# pidshield-mk-3_0.net
KiCad netlist of a schematic drawn in EAGLE
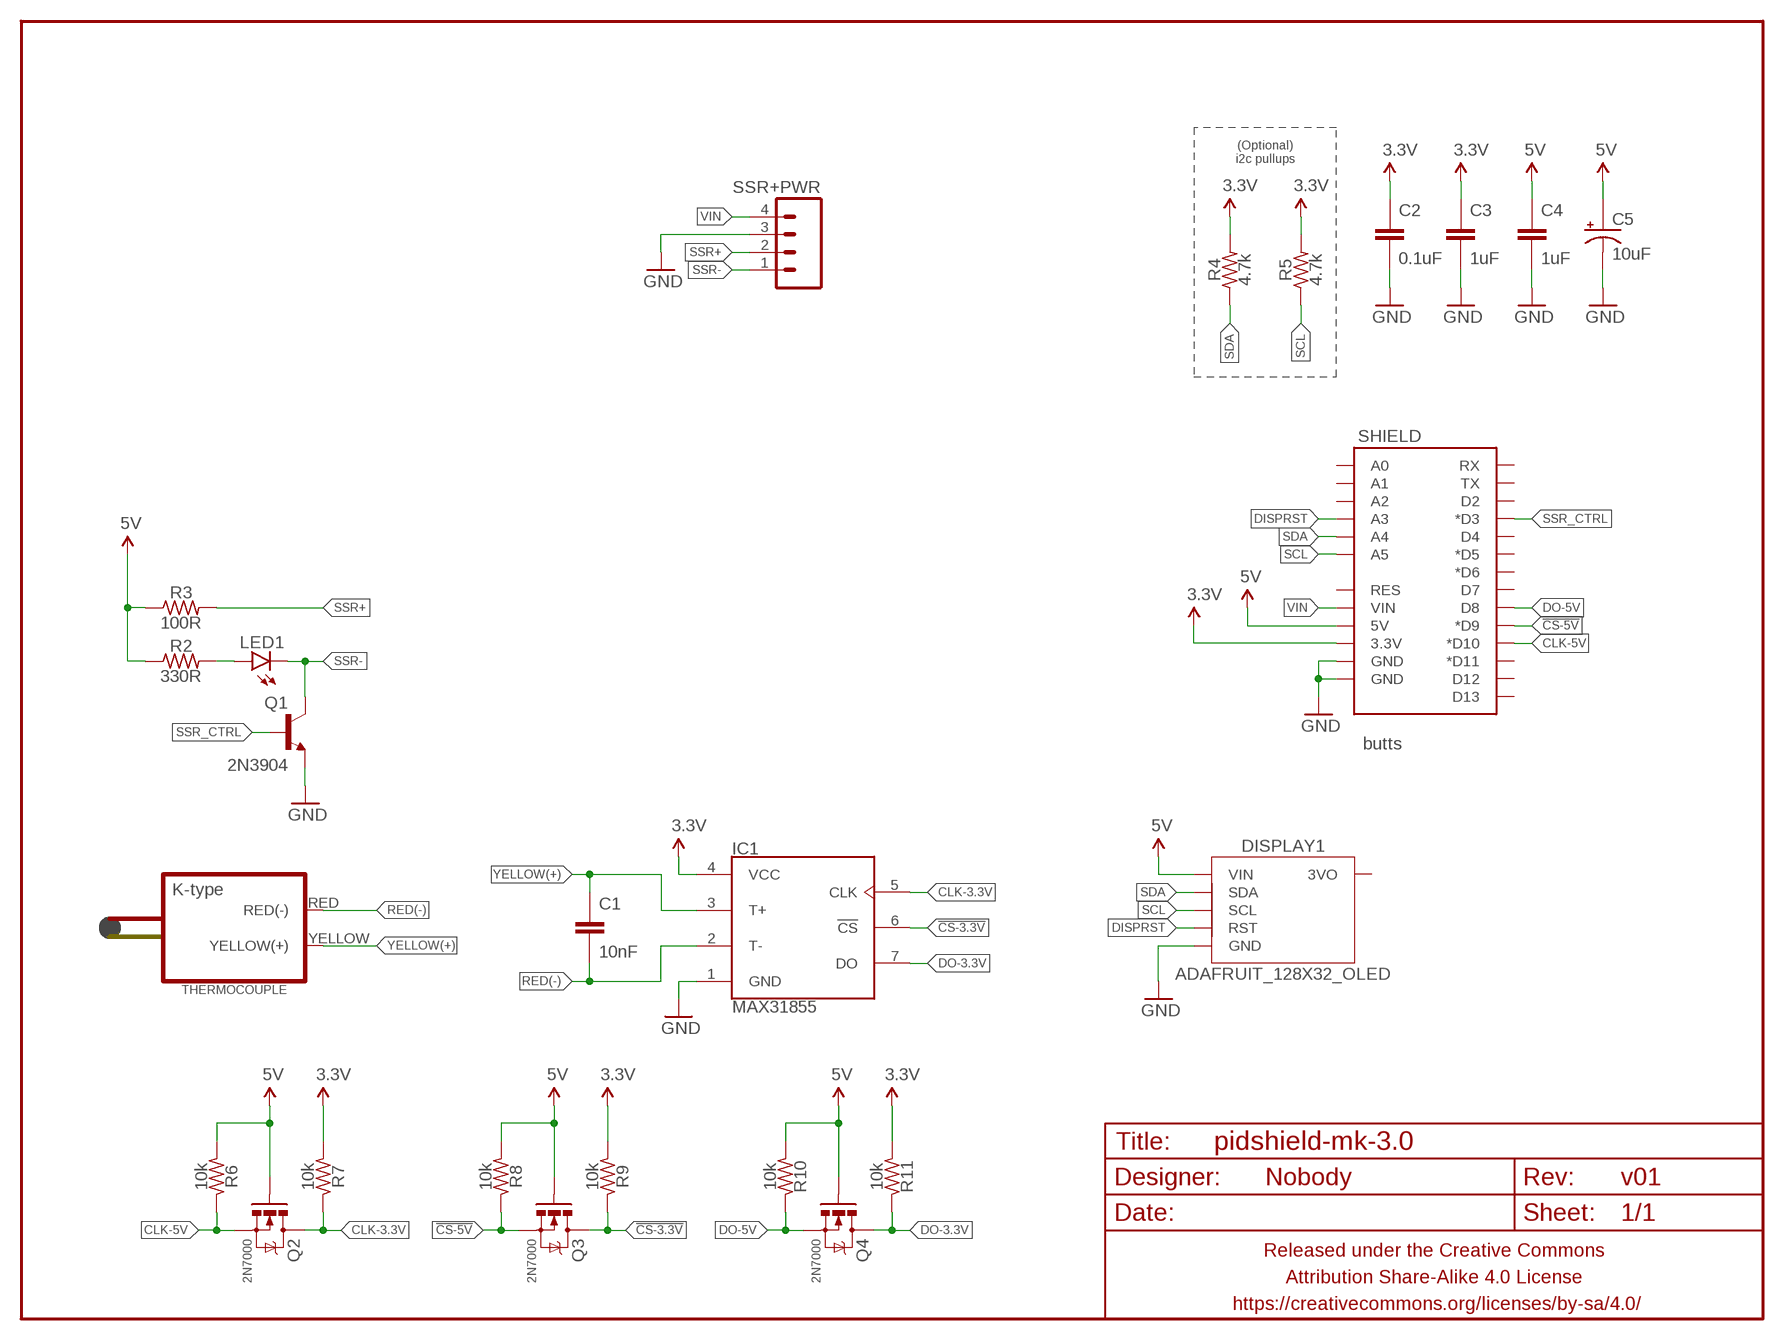
[diagram p0: schematic, sheet 1]

(export (version "E")
  (design (tool "Eeschema 10.0.6"))
  (components
    (comp (ref "C1")
      (value "10nF")
      (footprint "eagle-import:C0805")
      (libsource (lib "eagle-import") (part "CAPACITOR-CERAMICC0805"))
    )
    (comp (ref "C2")
      (value "0.1uF")
      (footprint "eagle-import:C025-024X044")
      (libsource (lib "eagle-import") (part "CAPACITOR-CERAMIC025-024X044"))
    )
    (comp (ref "C3")
      (value "1uF")
      (footprint "eagle-import:C025-024X044")
      (libsource (lib "eagle-import") (part "CAPACITOR-CERAMIC025-024X044"))
    )
    (comp (ref "C4")
      (value "1uF")
      (footprint "eagle-import:C025-024X044")
      (libsource (lib "eagle-import") (part "CAPACITOR-CERAMIC025-024X044"))
    )
    (comp (ref "C5")
      (value "10uF")
      (footprint "eagle-import:E2,5-6")
      (libsource (lib "eagle-import") (part "CAPACITOR-POLARIZEDE2.5-6"))
    )
    (comp (ref "DISPLAY1")
      (value "ADAFRUIT_128X32_OLED")
      (footprint "eagle-import:ADAFRUIT_128X32_OLED_I2C_CLOSER_NS")
      (libsource (lib "eagle-import") (part "ADAFRUIT_128X32_OLED_I2CNOSILK_NOHOLES_NOPROBLEM"))
    )
    (comp (ref "FRAME1")
      (value "FRAME-LETTERNO_PACKAGE")
      (footprint "eagle-import:DUMMY")
      (fields (field (name "DESIGNER") "Nobody"))
      (libsource (lib "eagle-import") (part "FRAME-LETTERNO_PACKAGE"))
    )
    (comp (ref "IC1")
      (value "MAX31855")
      (footprint "eagle-import:SOIC127P600X175-8N")
      (libsource (lib "eagle-import") (part "MAX31855SOIC"))
    )
    (comp (ref "LED1")
      (value "LED3MM-LESS")
      (footprint "eagle-import:LED3MM-LESSSILK")
      (libsource (lib "eagle-import") (part "LED3MM-LESS"))
    )
    (comp (ref "Q1")
      (value "2N3904")
      (footprint "eagle-import:TO-92-AMMO")
      (libsource (lib "eagle-import") (part "TRANSISTOR_NPNTO-92-AMMO-EBC"))
    )
    (comp (ref "Q2")
      (value "2N7000")
      (footprint "eagle-import:TO-92-AMMO")
      (libsource (lib "eagle-import") (part "MOSFET-NCHANNEL2N7000-AMMO"))
    )
    (comp (ref "Q3")
      (value "2N7000")
      (footprint "eagle-import:TO-92-AMMO")
      (libsource (lib "eagle-import") (part "MOSFET-NCHANNEL2N7000-AMMO"))
    )
    (comp (ref "Q4")
      (value "2N7000")
      (footprint "eagle-import:TO-92-AMMO")
      (libsource (lib "eagle-import") (part "MOSFET-NCHANNEL2N7000-AMMO"))
    )
    (comp (ref "R2")
      (value "330R")
      (footprint "eagle-import:RESISTOR-AXIAL-PTH-5.08MM")
      (libsource (lib "eagle-import") (part "RESISTORPTH-AXIAL-5.08MM"))
    )
    (comp (ref "R3")
      (value "100R")
      (footprint "eagle-import:RESISTOR-AXIAL-PTH-5.08MM")
      (libsource (lib "eagle-import") (part "RESISTORPTH-AXIAL-5.08MM"))
    )
    (comp (ref "R4")
      (value "4.7k")
      (footprint "eagle-import:RESISTOR-AXIAL-PTH-5.08MM")
      (libsource (lib "eagle-import") (part "RESISTORPTH-AXIAL-5.08MM"))
    )
    (comp (ref "R5")
      (value "4.7k")
      (footprint "eagle-import:RESISTOR-AXIAL-PTH-5.08MM")
      (libsource (lib "eagle-import") (part "RESISTORPTH-AXIAL-5.08MM"))
    )
    (comp (ref "R6")
      (value "10k")
      (footprint "eagle-import:RESISTOR-AXIAL-PTH-5.08MM")
      (libsource (lib "eagle-import") (part "RESISTORPTH-AXIAL-5.08MM"))
    )
    (comp (ref "R7")
      (value "10k")
      (footprint "eagle-import:RESISTOR-AXIAL-PTH-5.08MM")
      (libsource (lib "eagle-import") (part "RESISTORPTH-AXIAL-5.08MM"))
    )
    (comp (ref "R8")
      (value "10k")
      (footprint "eagle-import:RESISTOR-AXIAL-PTH-5.08MM")
      (libsource (lib "eagle-import") (part "RESISTORPTH-AXIAL-5.08MM"))
    )
    (comp (ref "R9")
      (value "10k")
      (footprint "eagle-import:RESISTOR-AXIAL-PTH-5.08MM")
      (libsource (lib "eagle-import") (part "RESISTORPTH-AXIAL-5.08MM"))
    )
    (comp (ref "R10")
      (value "10k")
      (footprint "eagle-import:RESISTOR-AXIAL-PTH-5.08MM")
      (libsource (lib "eagle-import") (part "RESISTORPTH-AXIAL-5.08MM"))
    )
    (comp (ref "R11")
      (value "10k")
      (footprint "eagle-import:RESISTOR-AXIAL-PTH-5.08MM")
      (libsource (lib "eagle-import") (part "RESISTORPTH-AXIAL-5.08MM"))
    )
    (comp (ref "SHIELD")
      (value "butts")
      (footprint "eagle-import:ARDUINO_SHIELD_SMALLER_NEKKID")
      (libsource (lib "eagle-import") (part "ARDUINO_SHIELD_SMALLERNEKKID"))
    )
    (comp (ref "SSR+PWR")
      (value "M04JST_XH_RA")
      (footprint "eagle-import:JST-4-XH-RA-PTH")
      (libsource (lib "eagle-import") (part "M04JST_XH_RA"))
    )
    (comp (ref "THERMOCOUPLE")
      (value "THERMOCOUPLE-CONNECTORMINI-PCB")
      (footprint "eagle-import:PCC-SMP")
      (libsource (lib "eagle-import") (part "THERMOCOUPLE-CONNECTORMINI-PCB"))
    )
  )
  (nets
    (net (code "1") (name "/~{CS-3.3V}") (class "Default")
      (node (ref "IC1") (pin "6") (pinfunction "~{CS}_6") (pintype "input"))
      (node (ref "Q3") (pin "3") (pinfunction "D_3") (pintype "passive"))
      (node (ref "R9") (pin "P$1") (pinfunction "1_P$1") (pintype "passive"))
    )
    (net (code "2") (name "/~{CS-5V}") (class "Default")
      (node (ref "Q3") (pin "1") (pinfunction "S_1") (pintype "passive"))
      (node (ref "R8") (pin "P$1") (pinfunction "1_P$1") (pintype "passive"))
      (node (ref "SHIELD") (pin "D9") (pinfunction "*D9_D9") (pintype "bidirectional"))
    )
    (net (code "3") (name "3.3V") (class "Default")
      (node (ref "C2") (pin "1") (pinfunction "1_1") (pintype "passive"))
      (node (ref "C3") (pin "1") (pinfunction "1_1") (pintype "passive"))
      (node (ref "IC1") (pin "4") (pinfunction "VCC_4") (pintype "power_in"))
      (node (ref "R11") (pin "P$2") (pinfunction "2_P$2") (pintype "passive"))
      (node (ref "R4") (pin "P$2") (pinfunction "2_P$2") (pintype "passive"))
      (node (ref "R5") (pin "P$2") (pinfunction "2_P$2") (pintype "passive"))
      (node (ref "R7") (pin "P$2") (pinfunction "2_P$2") (pintype "passive"))
      (node (ref "R9") (pin "P$2") (pinfunction "2_P$2") (pintype "passive"))
      (node (ref "SHIELD") (pin "3.3V") (pinfunction "3.3V_3.3V") (pintype "bidirectional"))
    )
    (net (code "4") (name "5V") (class "Default")
      (node (ref "C4") (pin "1") (pinfunction "1_1") (pintype "passive"))
      (node (ref "C5") (pin "+") (pinfunction "+_+") (pintype "passive"))
      (node (ref "DISPLAY1") (pin "VIN") (pinfunction "VIN_VIN") (pintype "bidirectional"))
      (node (ref "Q2") (pin "2") (pinfunction "G_2") (pintype "passive"))
      (node (ref "Q3") (pin "2") (pinfunction "G_2") (pintype "passive"))
      (node (ref "Q4") (pin "2") (pinfunction "G_2") (pintype "passive"))
      (node (ref "R10") (pin "P$2") (pinfunction "2_P$2") (pintype "passive"))
      (node (ref "R2") (pin "P$1") (pinfunction "1_P$1") (pintype "passive"))
      (node (ref "R3") (pin "P$1") (pinfunction "1_P$1") (pintype "passive"))
      (node (ref "R6") (pin "P$2") (pinfunction "2_P$2") (pintype "passive"))
      (node (ref "R8") (pin "P$2") (pinfunction "2_P$2") (pintype "passive"))
      (node (ref "SHIELD") (pin "5V") (pinfunction "5V_5V") (pintype "bidirectional"))
    )
    (net (code "5") (name "CLK-3.3V") (class "Default")
      (node (ref "IC1") (pin "5") (pinfunction "CLK_5") (pintype "input"))
      (node (ref "Q2") (pin "3") (pinfunction "D_3") (pintype "passive"))
      (node (ref "R7") (pin "P$1") (pinfunction "1_P$1") (pintype "passive"))
    )
    (net (code "6") (name "CLK-5V") (class "Default")
      (node (ref "Q2") (pin "1") (pinfunction "S_1") (pintype "passive"))
      (node (ref "R6") (pin "P$1") (pinfunction "1_P$1") (pintype "passive"))
      (node (ref "SHIELD") (pin "D10") (pinfunction "*D10_D10") (pintype "bidirectional"))
    )
    (net (code "7") (name "DISPRST") (class "Default")
      (node (ref "DISPLAY1") (pin "RST") (pinfunction "RST_RST") (pintype "bidirectional"))
      (node (ref "SHIELD") (pin "A3") (pinfunction "A3_A3") (pintype "bidirectional"))
    )
    (net (code "8") (name "DO-3.3V") (class "Default")
      (node (ref "IC1") (pin "7") (pinfunction "DO_7") (pintype "output"))
      (node (ref "Q4") (pin "3") (pinfunction "D_3") (pintype "passive"))
      (node (ref "R11") (pin "P$1") (pinfunction "1_P$1") (pintype "passive"))
    )
    (net (code "9") (name "DO-5V") (class "Default")
      (node (ref "Q4") (pin "1") (pinfunction "S_1") (pintype "passive"))
      (node (ref "R10") (pin "P$1") (pinfunction "1_P$1") (pintype "passive"))
      (node (ref "SHIELD") (pin "D8") (pinfunction "D8_D8") (pintype "bidirectional"))
    )
    (net (code "10") (name "GND") (class "Default")
      (node (ref "C2") (pin "2") (pinfunction "2_2") (pintype "passive"))
      (node (ref "C3") (pin "2") (pinfunction "2_2") (pintype "passive"))
      (node (ref "C4") (pin "2") (pinfunction "2_2") (pintype "passive"))
      (node (ref "C5") (pin "-") (pinfunction "-_-") (pintype "passive"))
      (node (ref "DISPLAY1") (pin "GND") (pinfunction "GND_GND") (pintype "bidirectional"))
      (node (ref "IC1") (pin "1") (pinfunction "GND_1") (pintype "power_in"))
      (node (ref "Q1") (pin "1") (pinfunction "E_1") (pintype "passive"))
      (node (ref "SHIELD") (pin "GND@0") (pinfunction "GND_GND@0") (pintype "bidirectional"))
      (node (ref "SHIELD") (pin "GND@1") (pinfunction "GND_GND@1") (pintype "bidirectional"))
      (node (ref "SSR+PWR") (pin "3") (pinfunction "3_3") (pintype "passive"))
    )
    (net (code "11") (name "Net-(R2-2)") (class "Default")
      (node (ref "LED1") (pin "A") (pinfunction "A_A") (pintype "passive"))
      (node (ref "R2") (pin "P$2") (pinfunction "2_P$2") (pintype "passive"))
    )
    (net (code "12") (name "RED(-)") (class "Default")
      (node (ref "C1") (pin "2") (pinfunction "2_2") (pintype "passive"))
      (node (ref "IC1") (pin "2") (pinfunction "T-_2") (pintype "input"))
      (node (ref "THERMOCOUPLE") (pin "RED") (pinfunction "RED(-)_RED") (pintype "bidirectional"))
    )
    (net (code "13") (name "SCL") (class "Default")
      (node (ref "DISPLAY1") (pin "SCL") (pinfunction "SCL_SCL") (pintype "bidirectional"))
      (node (ref "R5") (pin "P$1") (pinfunction "1_P$1") (pintype "passive"))
      (node (ref "SHIELD") (pin "A5") (pinfunction "A5_A5") (pintype "bidirectional"))
    )
    (net (code "14") (name "SDA") (class "Default")
      (node (ref "DISPLAY1") (pin "SDA") (pinfunction "SDA_SDA") (pintype "bidirectional"))
      (node (ref "R4") (pin "P$1") (pinfunction "1_P$1") (pintype "passive"))
      (node (ref "SHIELD") (pin "A4") (pinfunction "A4_A4") (pintype "bidirectional"))
    )
    (net (code "15") (name "SSR+") (class "Default")
      (node (ref "R3") (pin "P$2") (pinfunction "2_P$2") (pintype "passive"))
      (node (ref "SSR+PWR") (pin "2") (pinfunction "2_2") (pintype "passive"))
    )
    (net (code "16") (name "SSR-") (class "Default")
      (node (ref "LED1") (pin "K") (pinfunction "C_K") (pintype "passive"))
      (node (ref "Q1") (pin "3") (pinfunction "C_3") (pintype "passive"))
      (node (ref "SSR+PWR") (pin "1") (pinfunction "1_1") (pintype "passive"))
    )
    (net (code "17") (name "SSR_CTRL") (class "Default")
      (node (ref "Q1") (pin "2") (pinfunction "B_2") (pintype "passive"))
      (node (ref "SHIELD") (pin "D3") (pinfunction "*D3_D3") (pintype "bidirectional"))
    )
    (net (code "18") (name "VIN") (class "Default")
      (node (ref "SHIELD") (pin "VIN") (pinfunction "VIN_VIN") (pintype "bidirectional"))
      (node (ref "SSR+PWR") (pin "4") (pinfunction "4_4") (pintype "passive"))
    )
    (net (code "19") (name "YELLOW(+)") (class "Default")
      (node (ref "C1") (pin "1") (pinfunction "1_1") (pintype "passive"))
      (node (ref "IC1") (pin "3") (pinfunction "T+_3") (pintype "input"))
      (node (ref "THERMOCOUPLE") (pin "YELLOW") (pinfunction "YELLOW(+)_YELLOW") (pintype "bidirectional"))
    )
    (net (code "20") (name "unconnected-(DISPLAY1-Pad3VO)") (class "Default")
      (node (ref "DISPLAY1") (pin "3VO") (pinfunction "3VO_3VO") (pintype "bidirectional"))
    )
    (net (code "21") (name "unconnected-(SHIELD-*D5-PadD5)") (class "Default")
      (node (ref "SHIELD") (pin "D5") (pinfunction "*D5_D5") (pintype "bidirectional"))
    )
    (net (code "22") (name "unconnected-(SHIELD-*D6-PadD6)") (class "Default")
      (node (ref "SHIELD") (pin "D6") (pinfunction "*D6_D6") (pintype "bidirectional"))
    )
    (net (code "23") (name "unconnected-(SHIELD-*D11-PadD11)") (class "Default")
      (node (ref "SHIELD") (pin "D11") (pinfunction "*D11_D11") (pintype "bidirectional"))
    )
    (net (code "24") (name "unconnected-(SHIELD-PadA0)") (class "Default")
      (node (ref "SHIELD") (pin "A0") (pinfunction "A0_A0") (pintype "bidirectional"))
    )
    (net (code "25") (name "unconnected-(SHIELD-PadA1)") (class "Default")
      (node (ref "SHIELD") (pin "A1") (pinfunction "A1_A1") (pintype "bidirectional"))
    )
    (net (code "26") (name "unconnected-(SHIELD-PadA2)") (class "Default")
      (node (ref "SHIELD") (pin "A2") (pinfunction "A2_A2") (pintype "bidirectional"))
    )
    (net (code "27") (name "unconnected-(SHIELD-PadD2)") (class "Default")
      (node (ref "SHIELD") (pin "D2") (pinfunction "D2_D2") (pintype "bidirectional"))
    )
    (net (code "28") (name "unconnected-(SHIELD-PadD4)") (class "Default")
      (node (ref "SHIELD") (pin "D4") (pinfunction "D4_D4") (pintype "bidirectional"))
    )
    (net (code "29") (name "unconnected-(SHIELD-PadD7)") (class "Default")
      (node (ref "SHIELD") (pin "D7") (pinfunction "D7_D7") (pintype "bidirectional"))
    )
    (net (code "30") (name "unconnected-(SHIELD-PadD12)") (class "Default")
      (node (ref "SHIELD") (pin "D12") (pinfunction "D12_D12") (pintype "bidirectional"))
    )
    (net (code "31") (name "unconnected-(SHIELD-PadD13)") (class "Default")
      (node (ref "SHIELD") (pin "D13") (pinfunction "D13_D13") (pintype "bidirectional"))
    )
    (net (code "32") (name "unconnected-(SHIELD-PadRES)") (class "Default")
      (node (ref "SHIELD") (pin "RES") (pinfunction "RES_RES") (pintype "bidirectional"))
    )
    (net (code "33") (name "unconnected-(SHIELD-PadRX)") (class "Default")
      (node (ref "SHIELD") (pin "RX") (pinfunction "RX_RX") (pintype "bidirectional"))
    )
    (net (code "34") (name "unconnected-(SHIELD-PadTX)") (class "Default")
      (node (ref "SHIELD") (pin "TX") (pinfunction "TX_TX") (pintype "bidirectional"))
    )
  )
)
